# F800_Rear_wire.net
KiCad netlist of a schematic drawn in Altium Designer
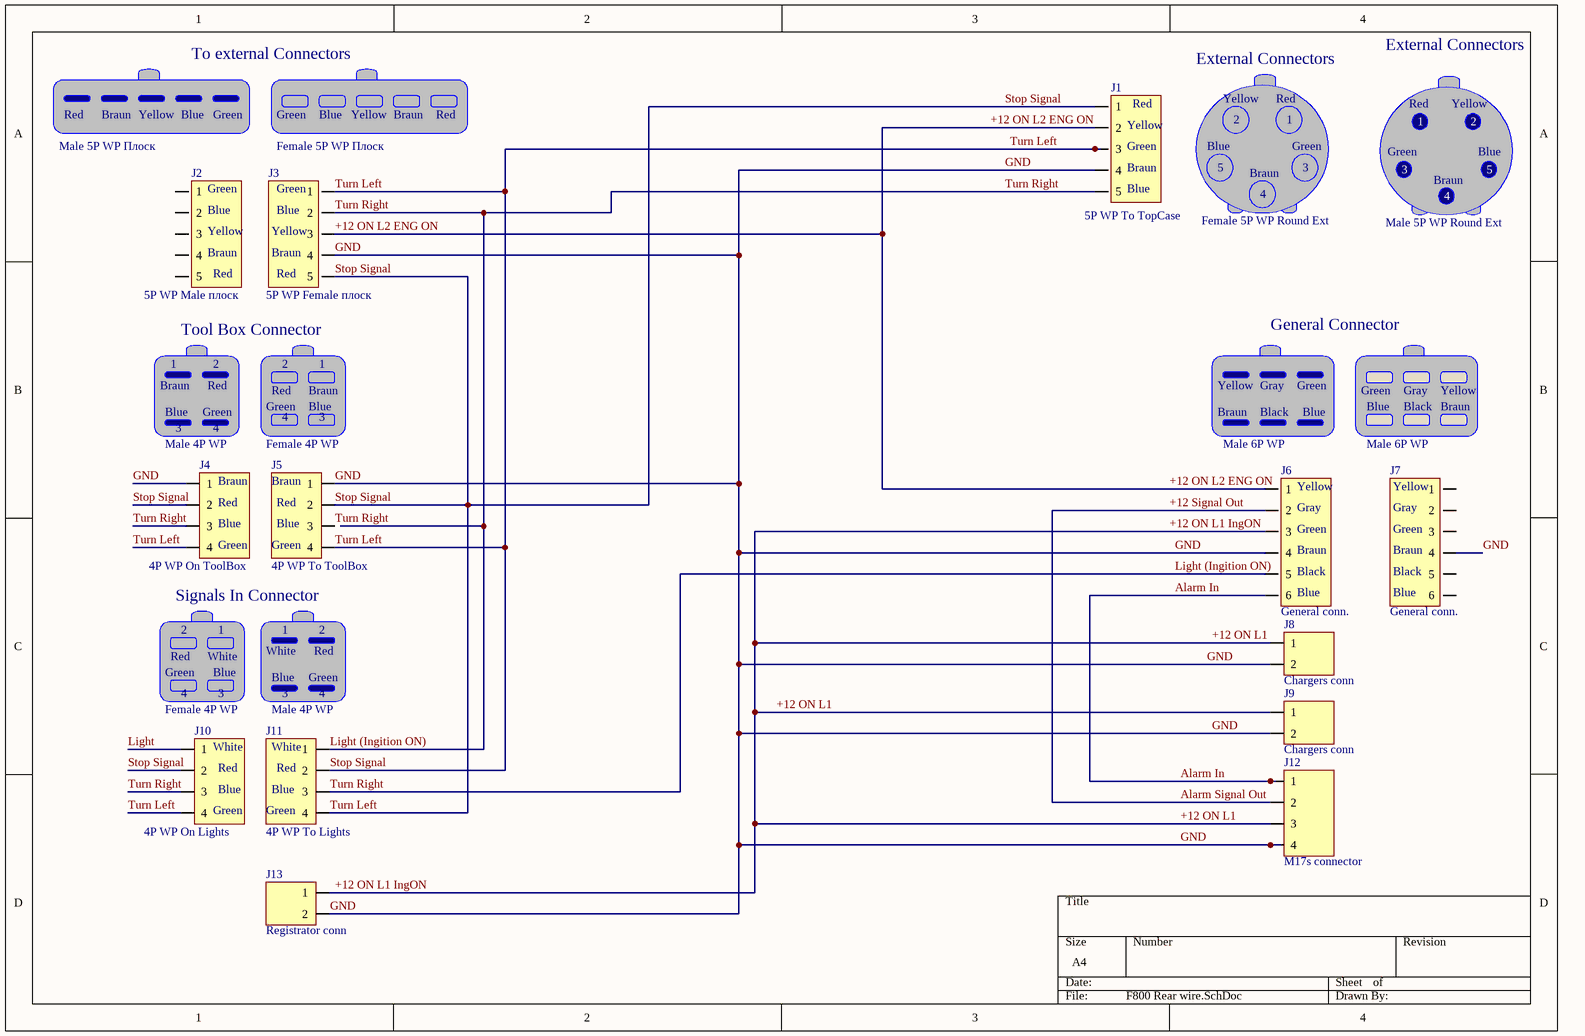
[diagram p0: F800 Rear wire.SchDoc]

(export (version "E")
  (design (tool "Eeschema 10.0.6"))
  (components
    (comp (ref "J1")
      (value "5P WP To TopCase")
      (footprint "Connector:Line 2.54 x 5")
      (description "Vert, Sgl line, Male")
      (libsource (lib "Connector") (part "PLS-5"))
    )
    (comp (ref "J2")
      (value "5P WP Male плоск")
      (footprint "Connector:Line 2.54 x 5")
      (description "Vert, Sgl line, Male")
      (libsource (lib "Connector") (part "PLS-5"))
    )
    (comp (ref "J3")
      (value "5P WP Female плоск")
      (footprint "Connector:Line 2.54 x 5")
      (description "Vert, Sgl line, Male")
      (libsource (lib "") (part "PLS-5_1"))
    )
    (comp (ref "J4")
      (value "4P WP On ToolBox")
      (footprint "Connector:Line 2.54 X 4")
      (description "Vert, Sgl line, Male")
      (libsource (lib "Connector") (part "PLS-4"))
    )
    (comp (ref "J5")
      (value "4P WP To ToolBox")
      (footprint "Connector:Line 2.54 X 4")
      (description "Vert, Sgl line, Male")
      (libsource (lib "") (part "PLS-4_1"))
    )
    (comp (ref "J6")
      (value "General conn.")
      (footprint "Connector:Line 2.54 x 6")
      (description "Vert, Sgl line, Male")
      (libsource (lib "Connector") (part "PLS-6"))
    )
    (comp (ref "J7")
      (value "General conn.")
      (footprint "Connector:Line 2.54 x 6")
      (description "Vert, Sgl line, Male")
      (libsource (lib "") (part "PLS-6_1"))
    )
    (comp (ref "J8")
      (value "Chargers conn")
      (footprint "Connector:Line 2.54 x 2")
      (description "Vert, Sgl line, Male")
      (libsource (lib "Connector") (part "PLS-2"))
    )
    (comp (ref "J9")
      (value "Chargers conn")
      (footprint "Connector:Line 2.54 x 2")
      (description "Vert, Sgl line, Male")
      (libsource (lib "Connector") (part "PLS-2"))
    )
    (comp (ref "J10")
      (value "4P WP On Lights")
      (footprint "Connector:Line 2.54 X 4")
      (description "Vert, Sgl line, Male")
      (libsource (lib "Connector") (part "PLS-4"))
    )
    (comp (ref "J11")
      (value "4P WP To Lights")
      (footprint "Connector:Line 2.54 X 4")
      (description "Vert, Sgl line, Male")
      (libsource (lib "") (part "PLS-4_1"))
    )
    (comp (ref "J12")
      (value "M17s connector")
      (footprint "Connector:Line 2.54 X 4")
      (description "Vert, Sgl line, Male")
      (libsource (lib "Connector") (part "PLS-4"))
    )
    (comp (ref "J13")
      (value "Registrator conn")
      (footprint "Connector:Line 2.54 x 2")
      (description "Vert, Sgl line, Male")
      (libsource (lib "") (part "PLS-2_1"))
    )
  )
  (nets
    (net (code "1") (name "/+12 ON L1") (class "Default")
      (node (ref "J12") (pin "3") (pinfunction "3_3") (pintype "passive"))
      (node (ref "J13") (pin "1") (pinfunction "1_1") (pintype "passive"))
      (node (ref "J6") (pin "3") (pinfunction "3_3") (pintype "passive"))
      (node (ref "J8") (pin "1") (pinfunction "1_1") (pintype "passive"))
      (node (ref "J9") (pin "1") (pinfunction "1_1") (pintype "passive"))
    )
    (net (code "2") (name "/+12 ON L2 ENG ON") (class "Default")
      (node (ref "J1") (pin "2") (pinfunction "2_2") (pintype "passive"))
      (node (ref "J3") (pin "3") (pinfunction "3_3") (pintype "passive"))
      (node (ref "J6") (pin "1") (pinfunction "1_1") (pintype "passive"))
    )
    (net (code "3") (name "/+12 Signal Out") (class "Default")
      (node (ref "J12") (pin "2") (pinfunction "2_2") (pintype "passive"))
      (node (ref "J6") (pin "2") (pinfunction "2_2") (pintype "passive"))
    )
    (net (code "4") (name "/Alarm In") (class "Default")
      (node (ref "J12") (pin "1") (pinfunction "1_1") (pintype "passive"))
      (node (ref "J6") (pin "6") (pinfunction "6_6") (pintype "passive"))
    )
    (net (code "5") (name "/GND") (class "Default")
      (node (ref "J1") (pin "4") (pinfunction "4_4") (pintype "passive"))
      (node (ref "J12") (pin "4") (pinfunction "4_4") (pintype "passive"))
      (node (ref "J13") (pin "2") (pinfunction "2_2") (pintype "passive"))
      (node (ref "J3") (pin "4") (pinfunction "4_4") (pintype "passive"))
      (node (ref "J4") (pin "1") (pinfunction "1_1") (pintype "passive"))
      (node (ref "J5") (pin "1") (pinfunction "1_1") (pintype "passive"))
      (node (ref "J6") (pin "4") (pinfunction "4_4") (pintype "passive"))
      (node (ref "J7") (pin "4") (pinfunction "4_4") (pintype "passive"))
      (node (ref "J8") (pin "2") (pinfunction "2_2") (pintype "passive"))
      (node (ref "J9") (pin "2") (pinfunction "2_2") (pintype "passive"))
    )
    (net (code "6") (name "/Light") (class "Default")
      (node (ref "J10") (pin "1") (pinfunction "1_1") (pintype "passive"))
    )
    (net (code "7") (name "/Light (Ingition ON)") (class "Default")
      (node (ref "J1") (pin "5") (pinfunction "5_5") (pintype "passive"))
      (node (ref "J10") (pin "3") (pinfunction "3_3") (pintype "passive"))
      (node (ref "J11") (pin "1") (pinfunction "1_1") (pintype "passive"))
      (node (ref "J11") (pin "3") (pinfunction "3_3") (pintype "passive"))
      (node (ref "J3") (pin "2") (pinfunction "2_2") (pintype "passive"))
      (node (ref "J4") (pin "3") (pinfunction "3_3") (pintype "passive"))
      (node (ref "J5") (pin "3") (pinfunction "3_3") (pintype "passive"))
      (node (ref "J6") (pin "5") (pinfunction "5_5") (pintype "passive"))
    )
    (net (code "8") (name "/Stop Signal") (class "Default")
      (node (ref "J1") (pin "1") (pinfunction "1_1") (pintype "passive"))
      (node (ref "J1") (pin "3") (pinfunction "3_3") (pintype "passive"))
      (node (ref "J10") (pin "2") (pinfunction "2_2") (pintype "passive"))
      (node (ref "J10") (pin "4") (pinfunction "4_4") (pintype "passive"))
      (node (ref "J11") (pin "2") (pinfunction "2_2") (pintype "passive"))
      (node (ref "J11") (pin "4") (pinfunction "4_4") (pintype "passive"))
      (node (ref "J3") (pin "1") (pinfunction "1_1") (pintype "passive"))
      (node (ref "J3") (pin "5") (pinfunction "5_5") (pintype "passive"))
      (node (ref "J4") (pin "2") (pinfunction "2_2") (pintype "passive"))
      (node (ref "J4") (pin "4") (pinfunction "4_4") (pintype "passive"))
      (node (ref "J5") (pin "2") (pinfunction "2_2") (pintype "passive"))
      (node (ref "J5") (pin "4") (pinfunction "4_4") (pintype "passive"))
    )
    (net (code "9") (name "unconnected-(J2-Pad1)") (class "Default")
      (node (ref "J2") (pin "1") (pinfunction "1_1") (pintype "passive"))
    )
    (net (code "10") (name "unconnected-(J2-Pad2)") (class "Default")
      (node (ref "J2") (pin "2") (pinfunction "2_2") (pintype "passive"))
    )
    (net (code "11") (name "unconnected-(J2-Pad3)") (class "Default")
      (node (ref "J2") (pin "3") (pinfunction "3_3") (pintype "passive"))
    )
    (net (code "12") (name "unconnected-(J2-Pad4)") (class "Default")
      (node (ref "J2") (pin "4") (pinfunction "4_4") (pintype "passive"))
    )
    (net (code "13") (name "unconnected-(J2-Pad5)") (class "Default")
      (node (ref "J2") (pin "5") (pinfunction "5_5") (pintype "passive"))
    )
    (net (code "14") (name "unconnected-(J7-Pad1)") (class "Default")
      (node (ref "J7") (pin "1") (pinfunction "1_1") (pintype "passive"))
    )
    (net (code "15") (name "unconnected-(J7-Pad2)") (class "Default")
      (node (ref "J7") (pin "2") (pinfunction "2_2") (pintype "passive"))
    )
    (net (code "16") (name "unconnected-(J7-Pad3)") (class "Default")
      (node (ref "J7") (pin "3") (pinfunction "3_3") (pintype "passive"))
    )
    (net (code "17") (name "unconnected-(J7-Pad5)") (class "Default")
      (node (ref "J7") (pin "5") (pinfunction "5_5") (pintype "passive"))
    )
    (net (code "18") (name "unconnected-(J7-Pad6)") (class "Default")
      (node (ref "J7") (pin "6") (pinfunction "6_6") (pintype "passive"))
    )
  )
)
